# Dual-Channel-OpAmp_V1.net
KiCad netlist of a schematic drawn in EAGLE
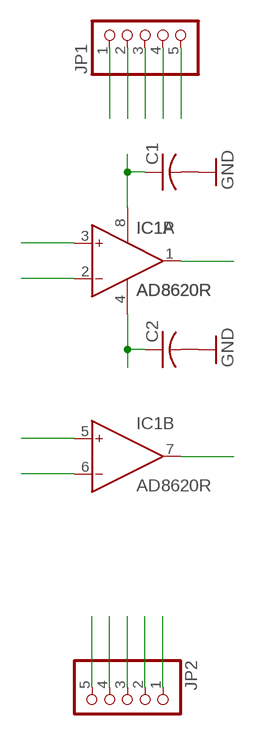
[diagram p0: schematic, sheet 1]

(export (version "E")
  (design (tool "Eeschema 10.0.6"))
  (components
    (comp (ref "C1")
      (value "C-USC0805")
      (footprint "eagle-import:C0805")
      (libsource (lib "eagle-import") (part "C-USC0805"))
    )
    (comp (ref "C2")
      (value "C-USC0805")
      (footprint "eagle-import:C0805")
      (libsource (lib "eagle-import") (part "C-USC0805"))
    )
    (comp (ref "IC1")
      (value "AD8620R")
      (footprint "eagle-import:SO8")
      (fields (field (name "MF") "ALTERA CORPORATION") (field (name "MPN") "AD8620ARZ"))
      (libsource (lib "eagle-import") (part "AD8620R"))
    )
    (comp (ref "JP1")
      (value "PINHD-1X5")
      (footprint "eagle-import:1X05")
      (libsource (lib "eagle-import") (part "PINHD-1X5"))
    )
    (comp (ref "JP2")
      (value "PINHD-1X5")
      (footprint "eagle-import:1X05")
      (libsource (lib "eagle-import") (part "PINHD-1X5"))
    )
  )
  (nets
    (net (code "1") (name "/1") (class "Default")
      (node (ref "IC1") (pin "1") (pinfunction "OUT_1") (pintype "output"))
      (node (ref "JP1") (pin "1") (pinfunction "1_1") (pintype "passive"))
    )
    (net (code "2") (name "/2") (class "Default")
      (node (ref "IC1") (pin "2") (pinfunction "IN-_2") (pintype "input"))
      (node (ref "JP1") (pin "2") (pinfunction "2_2") (pintype "passive"))
    )
    (net (code "3") (name "/3") (class "Default")
      (node (ref "IC1") (pin "3") (pinfunction "IN+_3") (pintype "input"))
      (node (ref "JP1") (pin "3") (pinfunction "3_3") (pintype "passive"))
    )
    (net (code "4") (name "/4") (class "Default")
      (node (ref "C2") (pin "1") (pinfunction "1_1") (pintype "passive"))
      (node (ref "IC1") (pin "4") (pinfunction "V-_4") (pintype "power_in"))
      (node (ref "JP1") (pin "4") (pinfunction "4_4") (pintype "passive"))
    )
    (net (code "5") (name "/5") (class "Default")
      (node (ref "IC1") (pin "5") (pinfunction "IN+_5") (pintype "input"))
      (node (ref "JP2") (pin "4") (pinfunction "4_4") (pintype "passive"))
    )
    (net (code "6") (name "/6") (class "Default")
      (node (ref "IC1") (pin "6") (pinfunction "IN-_6") (pintype "input"))
      (node (ref "JP2") (pin "3") (pinfunction "3_3") (pintype "passive"))
    )
    (net (code "7") (name "/7") (class "Default")
      (node (ref "IC1") (pin "7") (pinfunction "OUT_7") (pintype "output"))
      (node (ref "JP2") (pin "2") (pinfunction "2_2") (pintype "passive"))
    )
    (net (code "8") (name "/8") (class "Default")
      (node (ref "C1") (pin "1") (pinfunction "1_1") (pintype "passive"))
      (node (ref "IC1") (pin "8") (pinfunction "V+_8") (pintype "power_in"))
      (node (ref "JP2") (pin "1") (pinfunction "1_1") (pintype "passive"))
    )
    (net (code "9") (name "GND") (class "Default")
      (node (ref "C1") (pin "2") (pinfunction "2_2") (pintype "passive"))
      (node (ref "C2") (pin "2") (pinfunction "2_2") (pintype "passive"))
      (node (ref "JP1") (pin "5") (pinfunction "5_5") (pintype "passive"))
      (node (ref "JP2") (pin "5") (pinfunction "5_5") (pintype "passive"))
    )
  )
)
